# Dual_linear_VCA_chip_v2_1.net
KiCad netlist of a schematic drawn in EAGLE
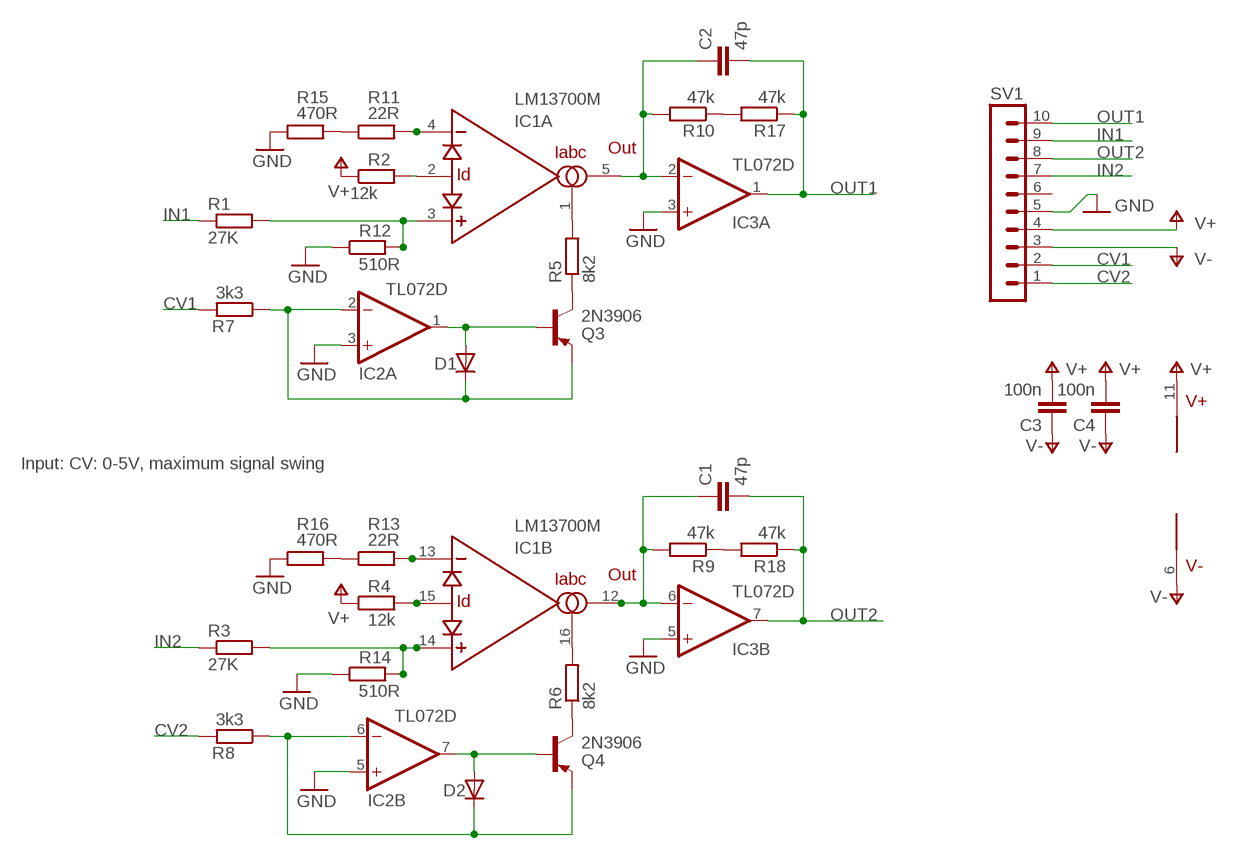
[diagram p0: schematic, sheet 1]

(export (version "E")
  (design (tool "Eeschema 10.0.6"))
  (components
    (comp (ref "C1")
      (value "47p")
      (footprint "eagle-import:C0805")
      (libsource (lib "eagle-import") (part "C-EUC0805"))
    )
    (comp (ref "C2")
      (value "47p")
      (footprint "eagle-import:C0805")
      (libsource (lib "eagle-import") (part "C-EUC0805"))
    )
    (comp (ref "C3")
      (value "100n")
      (footprint "eagle-import:C0805")
      (libsource (lib "eagle-import") (part "C-EUC0805"))
    )
    (comp (ref "C4")
      (value "100n")
      (footprint "eagle-import:C0805")
      (libsource (lib "eagle-import") (part "C-EUC0805"))
    )
    (comp (ref "D1")
      (value "DIODE-SOD80C")
      (footprint "eagle-import:SOD80C")
      (libsource (lib "eagle-import") (part "DIODE-SOD80C"))
    )
    (comp (ref "D2")
      (value "DIODE-SOD80C")
      (footprint "eagle-import:SOD80C")
      (libsource (lib "eagle-import") (part "DIODE-SOD80C"))
    )
    (comp (ref "IC1")
      (value "LM13700M")
      (footprint "eagle-import:SO16")
      (libsource (lib "eagle-import") (part "LM13700M"))
    )
    (comp (ref "IC2")
      (value "TL072D")
      (footprint "eagle-import:SO08")
      (libsource (lib "eagle-import") (part "TL072D"))
    )
    (comp (ref "IC3")
      (value "TL072D")
      (footprint "eagle-import:SO08")
      (libsource (lib "eagle-import") (part "TL072D"))
    )
    (comp (ref "Q3")
      (value "2N3906")
      (footprint "eagle-import:TO92")
      (libsource (lib "eagle-import") (part "2N3906"))
    )
    (comp (ref "Q4")
      (value "2N3906")
      (footprint "eagle-import:TO92")
      (libsource (lib "eagle-import") (part "2N3906"))
    )
    (comp (ref "R1")
      (value "27K")
      (footprint "eagle-import:R0805")
      (libsource (lib "eagle-import") (part "R-EU_R0805"))
    )
    (comp (ref "R2")
      (value "12k")
      (footprint "eagle-import:R0805")
      (libsource (lib "eagle-import") (part "R-EU_R0805"))
    )
    (comp (ref "R3")
      (value "27K")
      (footprint "eagle-import:R0805")
      (libsource (lib "eagle-import") (part "R-EU_R0805"))
    )
    (comp (ref "R4")
      (value "12k")
      (footprint "eagle-import:R0805")
      (libsource (lib "eagle-import") (part "R-EU_R0805"))
    )
    (comp (ref "R5")
      (value "8k2")
      (footprint "eagle-import:R0805")
      (libsource (lib "eagle-import") (part "R-EU_R0805"))
    )
    (comp (ref "R6")
      (value "8k2")
      (footprint "eagle-import:R0805")
      (libsource (lib "eagle-import") (part "R-EU_R0805"))
    )
    (comp (ref "R7")
      (value "3k3")
      (footprint "eagle-import:R0805")
      (libsource (lib "eagle-import") (part "R-EU_R0805"))
    )
    (comp (ref "R8")
      (value "3k3")
      (footprint "eagle-import:R0805")
      (libsource (lib "eagle-import") (part "R-EU_R0805"))
    )
    (comp (ref "R9")
      (value "47k")
      (footprint "eagle-import:R0805")
      (libsource (lib "eagle-import") (part "R-EU_R0805"))
    )
    (comp (ref "R10")
      (value "47k")
      (footprint "eagle-import:R0805")
      (libsource (lib "eagle-import") (part "R-EU_R0805"))
    )
    (comp (ref "R11")
      (value "22R")
      (footprint "eagle-import:R0805")
      (libsource (lib "eagle-import") (part "R-EU_R0805"))
    )
    (comp (ref "R12")
      (value "510R")
      (footprint "eagle-import:R0805")
      (libsource (lib "eagle-import") (part "R-EU_R0805"))
    )
    (comp (ref "R13")
      (value "22R")
      (footprint "eagle-import:R0805")
      (libsource (lib "eagle-import") (part "R-EU_R0805"))
    )
    (comp (ref "R14")
      (value "510R")
      (footprint "eagle-import:R0805")
      (libsource (lib "eagle-import") (part "R-EU_R0805"))
    )
    (comp (ref "R15")
      (value "470R")
      (footprint "eagle-import:R0805")
      (libsource (lib "eagle-import") (part "R-EU_R0805"))
    )
    (comp (ref "R16")
      (value "470R")
      (footprint "eagle-import:R0805")
      (libsource (lib "eagle-import") (part "R-EU_R0805"))
    )
    (comp (ref "R17")
      (value "47k")
      (footprint "eagle-import:R0805")
      (libsource (lib "eagle-import") (part "R-EU_R0805"))
    )
    (comp (ref "R18")
      (value "47k")
      (footprint "eagle-import:R0805")
      (libsource (lib "eagle-import") (part "R-EU_R0805"))
    )
    (comp (ref "SV1")
      (value "MA10-1")
      (footprint "eagle-import:MA10-1")
      (libsource (lib "eagle-import") (part "MA10-1"))
    )
  )
  (nets
    (net (code "1") (name "/CV1") (class "Default")
      (node (ref "R7") (pin "2") (pinfunction "2_2") (pintype "passive"))
      (node (ref "SV1") (pin "2") (pinfunction "2_2") (pintype "passive"))
    )
    (net (code "2") (name "/CV2") (class "Default")
      (node (ref "R8") (pin "2") (pinfunction "2_2") (pintype "passive"))
      (node (ref "SV1") (pin "1") (pinfunction "1_1") (pintype "passive"))
    )
    (net (code "3") (name "/IN1") (class "Default")
      (node (ref "R1") (pin "1") (pinfunction "1_1") (pintype "passive"))
      (node (ref "SV1") (pin "9") (pinfunction "9_9") (pintype "passive"))
    )
    (net (code "4") (name "/IN2") (class "Default")
      (node (ref "R3") (pin "1") (pinfunction "1_1") (pintype "passive"))
      (node (ref "SV1") (pin "7") (pinfunction "7_7") (pintype "passive"))
    )
    (net (code "5") (name "/OUT1") (class "Default")
      (node (ref "C2") (pin "2") (pinfunction "2_2") (pintype "passive"))
      (node (ref "IC3") (pin "1") (pinfunction "OUT_1") (pintype "output"))
      (node (ref "R17") (pin "1") (pinfunction "1_1") (pintype "passive"))
      (node (ref "SV1") (pin "10") (pinfunction "10_10") (pintype "passive"))
    )
    (net (code "6") (name "/OUT2") (class "Default")
      (node (ref "C1") (pin "2") (pinfunction "2_2") (pintype "passive"))
      (node (ref "IC3") (pin "7") (pinfunction "OUT_7") (pintype "output"))
      (node (ref "R18") (pin "1") (pinfunction "1_1") (pintype "passive"))
      (node (ref "SV1") (pin "8") (pinfunction "8_8") (pintype "passive"))
    )
    (net (code "7") (name "GND") (class "Default")
      (node (ref "IC2") (pin "3") (pinfunction "+IN_3") (pintype "input"))
      (node (ref "IC2") (pin "5") (pinfunction "+IN_5") (pintype "input"))
      (node (ref "IC3") (pin "3") (pinfunction "+IN_3") (pintype "input"))
      (node (ref "IC3") (pin "5") (pinfunction "+IN_5") (pintype "input"))
      (node (ref "R12") (pin "1") (pinfunction "1_1") (pintype "passive"))
      (node (ref "R14") (pin "1") (pinfunction "1_1") (pintype "passive"))
      (node (ref "R15") (pin "1") (pinfunction "1_1") (pintype "passive"))
      (node (ref "R16") (pin "1") (pinfunction "1_1") (pintype "passive"))
      (node (ref "SV1") (pin "5") (pinfunction "5_5") (pintype "passive"))
    )
    (net (code "8") (name "Net-(IC1A-+IN)") (class "Default")
      (node (ref "IC1") (pin "3") (pinfunction "+IN_3") (pintype "bidirectional"))
      (node (ref "R1") (pin "2") (pinfunction "2_2") (pintype "passive"))
      (node (ref "R12") (pin "2") (pinfunction "2_2") (pintype "passive"))
    )
    (net (code "9") (name "Net-(IC1A--IN)") (class "Default")
      (node (ref "IC1") (pin "4") (pinfunction "-IN_4") (pintype "bidirectional"))
      (node (ref "R11") (pin "2") (pinfunction "2_2") (pintype "passive"))
    )
    (net (code "10") (name "Net-(IC1A-IABC)") (class "Default")
      (node (ref "IC1") (pin "1") (pinfunction "IABC_1") (pintype "bidirectional"))
      (node (ref "R5") (pin "2") (pinfunction "2_2") (pintype "passive"))
    )
    (net (code "11") (name "Net-(IC1A-ID)") (class "Default")
      (node (ref "IC1") (pin "2") (pinfunction "ID_2") (pintype "bidirectional"))
      (node (ref "R2") (pin "2") (pinfunction "2_2") (pintype "passive"))
    )
    (net (code "12") (name "Net-(IC1A-OUT)") (class "Default")
      (node (ref "C2") (pin "1") (pinfunction "1_1") (pintype "passive"))
      (node (ref "IC1") (pin "5") (pinfunction "OUT_5") (pintype "bidirectional"))
      (node (ref "IC3") (pin "2") (pinfunction "-IN_2") (pintype "input"))
      (node (ref "R10") (pin "2") (pinfunction "2_2") (pintype "passive"))
    )
    (net (code "13") (name "Net-(IC1B-+IN)") (class "Default")
      (node (ref "IC1") (pin "14") (pinfunction "+IN_14") (pintype "bidirectional"))
      (node (ref "R14") (pin "2") (pinfunction "2_2") (pintype "passive"))
      (node (ref "R3") (pin "2") (pinfunction "2_2") (pintype "passive"))
    )
    (net (code "14") (name "Net-(IC1B--IN)") (class "Default")
      (node (ref "IC1") (pin "13") (pinfunction "-IN_13") (pintype "bidirectional"))
      (node (ref "R13") (pin "2") (pinfunction "2_2") (pintype "passive"))
    )
    (net (code "15") (name "Net-(IC1B-IABC)") (class "Default")
      (node (ref "IC1") (pin "16") (pinfunction "IABC_16") (pintype "bidirectional"))
      (node (ref "R6") (pin "2") (pinfunction "2_2") (pintype "passive"))
    )
    (net (code "16") (name "Net-(IC1B-ID)") (class "Default")
      (node (ref "IC1") (pin "15") (pinfunction "ID_15") (pintype "bidirectional"))
      (node (ref "R4") (pin "2") (pinfunction "2_2") (pintype "passive"))
    )
    (net (code "17") (name "Net-(IC1B-OUT)") (class "Default")
      (node (ref "C1") (pin "1") (pinfunction "1_1") (pintype "passive"))
      (node (ref "IC1") (pin "12") (pinfunction "OUT_12") (pintype "bidirectional"))
      (node (ref "IC3") (pin "6") (pinfunction "-IN_6") (pintype "input"))
      (node (ref "R9") (pin "2") (pinfunction "2_2") (pintype "passive"))
    )
    (net (code "18") (name "Net-(IC2A--IN)") (class "Default")
      (node (ref "D1") (pin "C") (pinfunction "C_C") (pintype "passive"))
      (node (ref "IC2") (pin "2") (pinfunction "-IN_2") (pintype "input"))
      (node (ref "Q3") (pin "3") (pinfunction "E_3") (pintype "passive"))
      (node (ref "R7") (pin "1") (pinfunction "1_1") (pintype "passive"))
    )
    (net (code "19") (name "Net-(IC2A-OUT)") (class "Default")
      (node (ref "D1") (pin "A") (pinfunction "A_A") (pintype "passive"))
      (node (ref "IC2") (pin "1") (pinfunction "OUT_1") (pintype "output"))
      (node (ref "Q3") (pin "2") (pinfunction "B_2") (pintype "passive"))
    )
    (net (code "20") (name "Net-(IC2B--IN)") (class "Default")
      (node (ref "D2") (pin "C") (pinfunction "C_C") (pintype "passive"))
      (node (ref "IC2") (pin "6") (pinfunction "-IN_6") (pintype "input"))
      (node (ref "Q4") (pin "3") (pinfunction "E_3") (pintype "passive"))
      (node (ref "R8") (pin "1") (pinfunction "1_1") (pintype "passive"))
    )
    (net (code "21") (name "Net-(IC2B-OUT)") (class "Default")
      (node (ref "D2") (pin "A") (pinfunction "A_A") (pintype "passive"))
      (node (ref "IC2") (pin "7") (pinfunction "OUT_7") (pintype "output"))
      (node (ref "Q4") (pin "2") (pinfunction "B_2") (pintype "passive"))
    )
    (net (code "22") (name "Net-(Q3-C)") (class "Default")
      (node (ref "Q3") (pin "1") (pinfunction "C_1") (pintype "passive"))
      (node (ref "R5") (pin "1") (pinfunction "1_1") (pintype "passive"))
    )
    (net (code "23") (name "Net-(Q4-C)") (class "Default")
      (node (ref "Q4") (pin "1") (pinfunction "C_1") (pintype "passive"))
      (node (ref "R6") (pin "1") (pinfunction "1_1") (pintype "passive"))
    )
    (net (code "24") (name "Net-(R10-Pad1)") (class "Default")
      (node (ref "R10") (pin "1") (pinfunction "1_1") (pintype "passive"))
      (node (ref "R17") (pin "2") (pinfunction "2_2") (pintype "passive"))
    )
    (net (code "25") (name "Net-(R11-Pad1)") (class "Default")
      (node (ref "R11") (pin "1") (pinfunction "1_1") (pintype "passive"))
      (node (ref "R15") (pin "2") (pinfunction "2_2") (pintype "passive"))
    )
    (net (code "26") (name "Net-(R13-Pad1)") (class "Default")
      (node (ref "R13") (pin "1") (pinfunction "1_1") (pintype "passive"))
      (node (ref "R16") (pin "2") (pinfunction "2_2") (pintype "passive"))
    )
    (net (code "27") (name "Net-(R18-Pad2)") (class "Default")
      (node (ref "R18") (pin "2") (pinfunction "2_2") (pintype "passive"))
      (node (ref "R9") (pin "1") (pinfunction "1_1") (pintype "passive"))
    )
    (net (code "28") (name "V+") (class "Default")
      (node (ref "C3") (pin "2") (pinfunction "2_2") (pintype "passive"))
      (node (ref "C4") (pin "2") (pinfunction "2_2") (pintype "passive"))
      (node (ref "IC1") (pin "11") (pinfunction "V+_11") (pintype "bidirectional"))
      (node (ref "R2") (pin "1") (pinfunction "1_1") (pintype "passive"))
      (node (ref "R4") (pin "1") (pinfunction "1_1") (pintype "passive"))
      (node (ref "SV1") (pin "4") (pinfunction "4_4") (pintype "passive"))
    )
    (net (code "29") (name "V-") (class "Default")
      (node (ref "C3") (pin "1") (pinfunction "1_1") (pintype "passive"))
      (node (ref "C4") (pin "1") (pinfunction "1_1") (pintype "passive"))
      (node (ref "IC1") (pin "6") (pinfunction "V-_6") (pintype "bidirectional"))
      (node (ref "SV1") (pin "3") (pinfunction "3_3") (pintype "passive"))
    )
    (net (code "30") (name "unconnected-(SV1-Pad6)") (class "Default")
      (node (ref "SV1") (pin "6") (pinfunction "6_6") (pintype "passive"))
    )
  )
)
